# EXTERNAL_FAN.net
KiCad netlist of a schematic drawn in Altium Designer
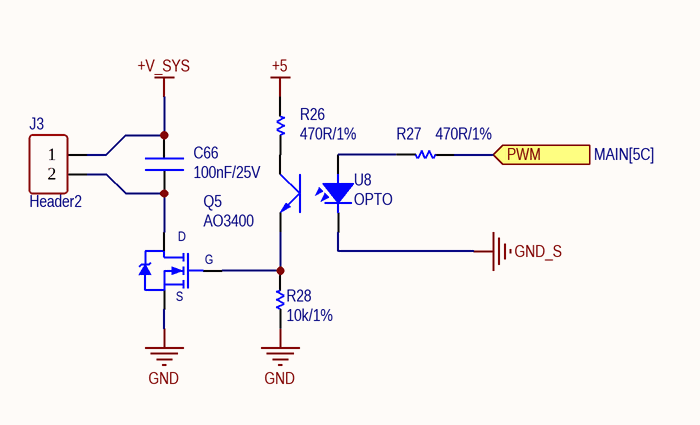
[diagram p0: EXTERNAL_FAN.SchDoc]

(export (version "E")
  (design (tool "Eeschema 10.0.6"))
  (components
    (comp (ref "C66")
      (value "100nF/25V")
      (footprint "CN-SMD-0603")
      (description "CL10B104KA8NNNC")
      (libsource (lib "Library") (part "CN"))
    )
    (comp (ref "J3")
      (value "Header2")
      (footprint "XH2.54-2-DIP")
      (description "Connector 2")
      (fields
        (field (name "MANUFACTURER") "Würth Elektronik eiSos GmbH")
        (field (name "PARTNO") "613002143121")
        (field (name "CREATED BY") "Karrer Zheng")
      )
      (libsource (lib "Library") (part "Header2"))
    )
    (comp (ref "Q5")
      (value "AO3400")
      (footprint "SOT23-123")
      (description "N-MOS 30V 5.8A")
      (libsource (lib "Library") (part "AO3400"))
    )
    (comp (ref "R26")
      (value "470R/1%")
      (footprint "RES-SMD-0603")
      (description "ERJ-1GJF4700C")
      (fields
        (field (name "MANUFACTURER") "Generic Components")
        (field (name "PUBLISHER") "Altium Hobart Technology Centre")
      )
      (libsource (lib "Library") (part "Res-SMD"))
    )
    (comp (ref "R27")
      (value "470R/1%")
      (footprint "RES-SMD-0603")
      (description "ERJ-1GJF4700C")
      (fields
        (field (name "MANUFACTURER") "Generic Components")
        (field (name "PUBLISHER") "Altium Hobart Technology Centre")
      )
      (libsource (lib "Library") (part "Res-SMD"))
    )
    (comp (ref "R28")
      (value "10k/1%")
      (footprint "RES-SMD-0603")
      (description "ERJ-3EKF1002V")
      (fields
        (field (name "MANUFACTURER") "Generic Components")
        (field (name "PUBLISHER") "Altium Hobart Technology Centre")
      )
      (libsource (lib "Library") (part "Res-SMD"))
    )
    (comp (ref "U8")
      (value "OPTO")
      (footprint "EL3H7")
      (description "EL3H7(B)(TA)-VG")
      (libsource (lib "Library") (part "OPTO"))
    )
  )
  (nets
    (net (code "1") (name "+5") (class "Default")
      (node (ref "R26") (pin "1") (pinfunction "1_1") (pintype "passive"))
    )
    (net (code "2") (name "+V_SYS") (class "Default")
      (node (ref "C66") (pin "1") (pinfunction "1_1") (pintype "passive"))
      (node (ref "J3") (pin "1") (pinfunction "1_1") (pintype "passive"))
    )
    (net (code "3") (name "/PWM") (class "Default")
      (node (ref "R27") (pin "1") (pinfunction "1_1") (pintype "passive"))
    )
    (net (code "4") (name "GND") (class "Default")
      (node (ref "Q5") (pin "3") (pinfunction "S_3") (pintype "passive"))
      (node (ref "R28") (pin "1") (pinfunction "1_1") (pintype "passive"))
    )
    (net (code "5") (name "GND_S") (class "Default")
      (node (ref "U8") (pin "K") (pinfunction "K_K") (pintype "passive"))
    )
    (net (code "6") (name "Net-(Q5-D)") (class "Default")
      (node (ref "C66") (pin "2") (pinfunction "2_2") (pintype "passive"))
      (node (ref "J3") (pin "2") (pinfunction "2_2") (pintype "passive"))
      (node (ref "Q5") (pin "2") (pinfunction "D_2") (pintype "passive"))
    )
    (net (code "7") (name "Net-(Q5-G)") (class "Default")
      (node (ref "Q5") (pin "1") (pinfunction "G_1") (pintype "passive"))
      (node (ref "R28") (pin "2") (pinfunction "2_2") (pintype "passive"))
      (node (ref "U8") (pin "E") (pinfunction "E_E") (pintype "passive"))
    )
    (net (code "8") (name "Net-(R26-Pad2)") (class "Default")
      (node (ref "R26") (pin "2") (pinfunction "2_2") (pintype "passive"))
      (node (ref "U8") (pin "C") (pinfunction "C_C") (pintype "passive"))
    )
    (net (code "9") (name "Net-(R27-Pad2)") (class "Default")
      (node (ref "R27") (pin "2") (pinfunction "2_2") (pintype "passive"))
      (node (ref "U8") (pin "A") (pinfunction "A_A") (pintype "passive"))
    )
  )
)
